# main.net
KiCad netlist of a schematic drawn in Altium Designer
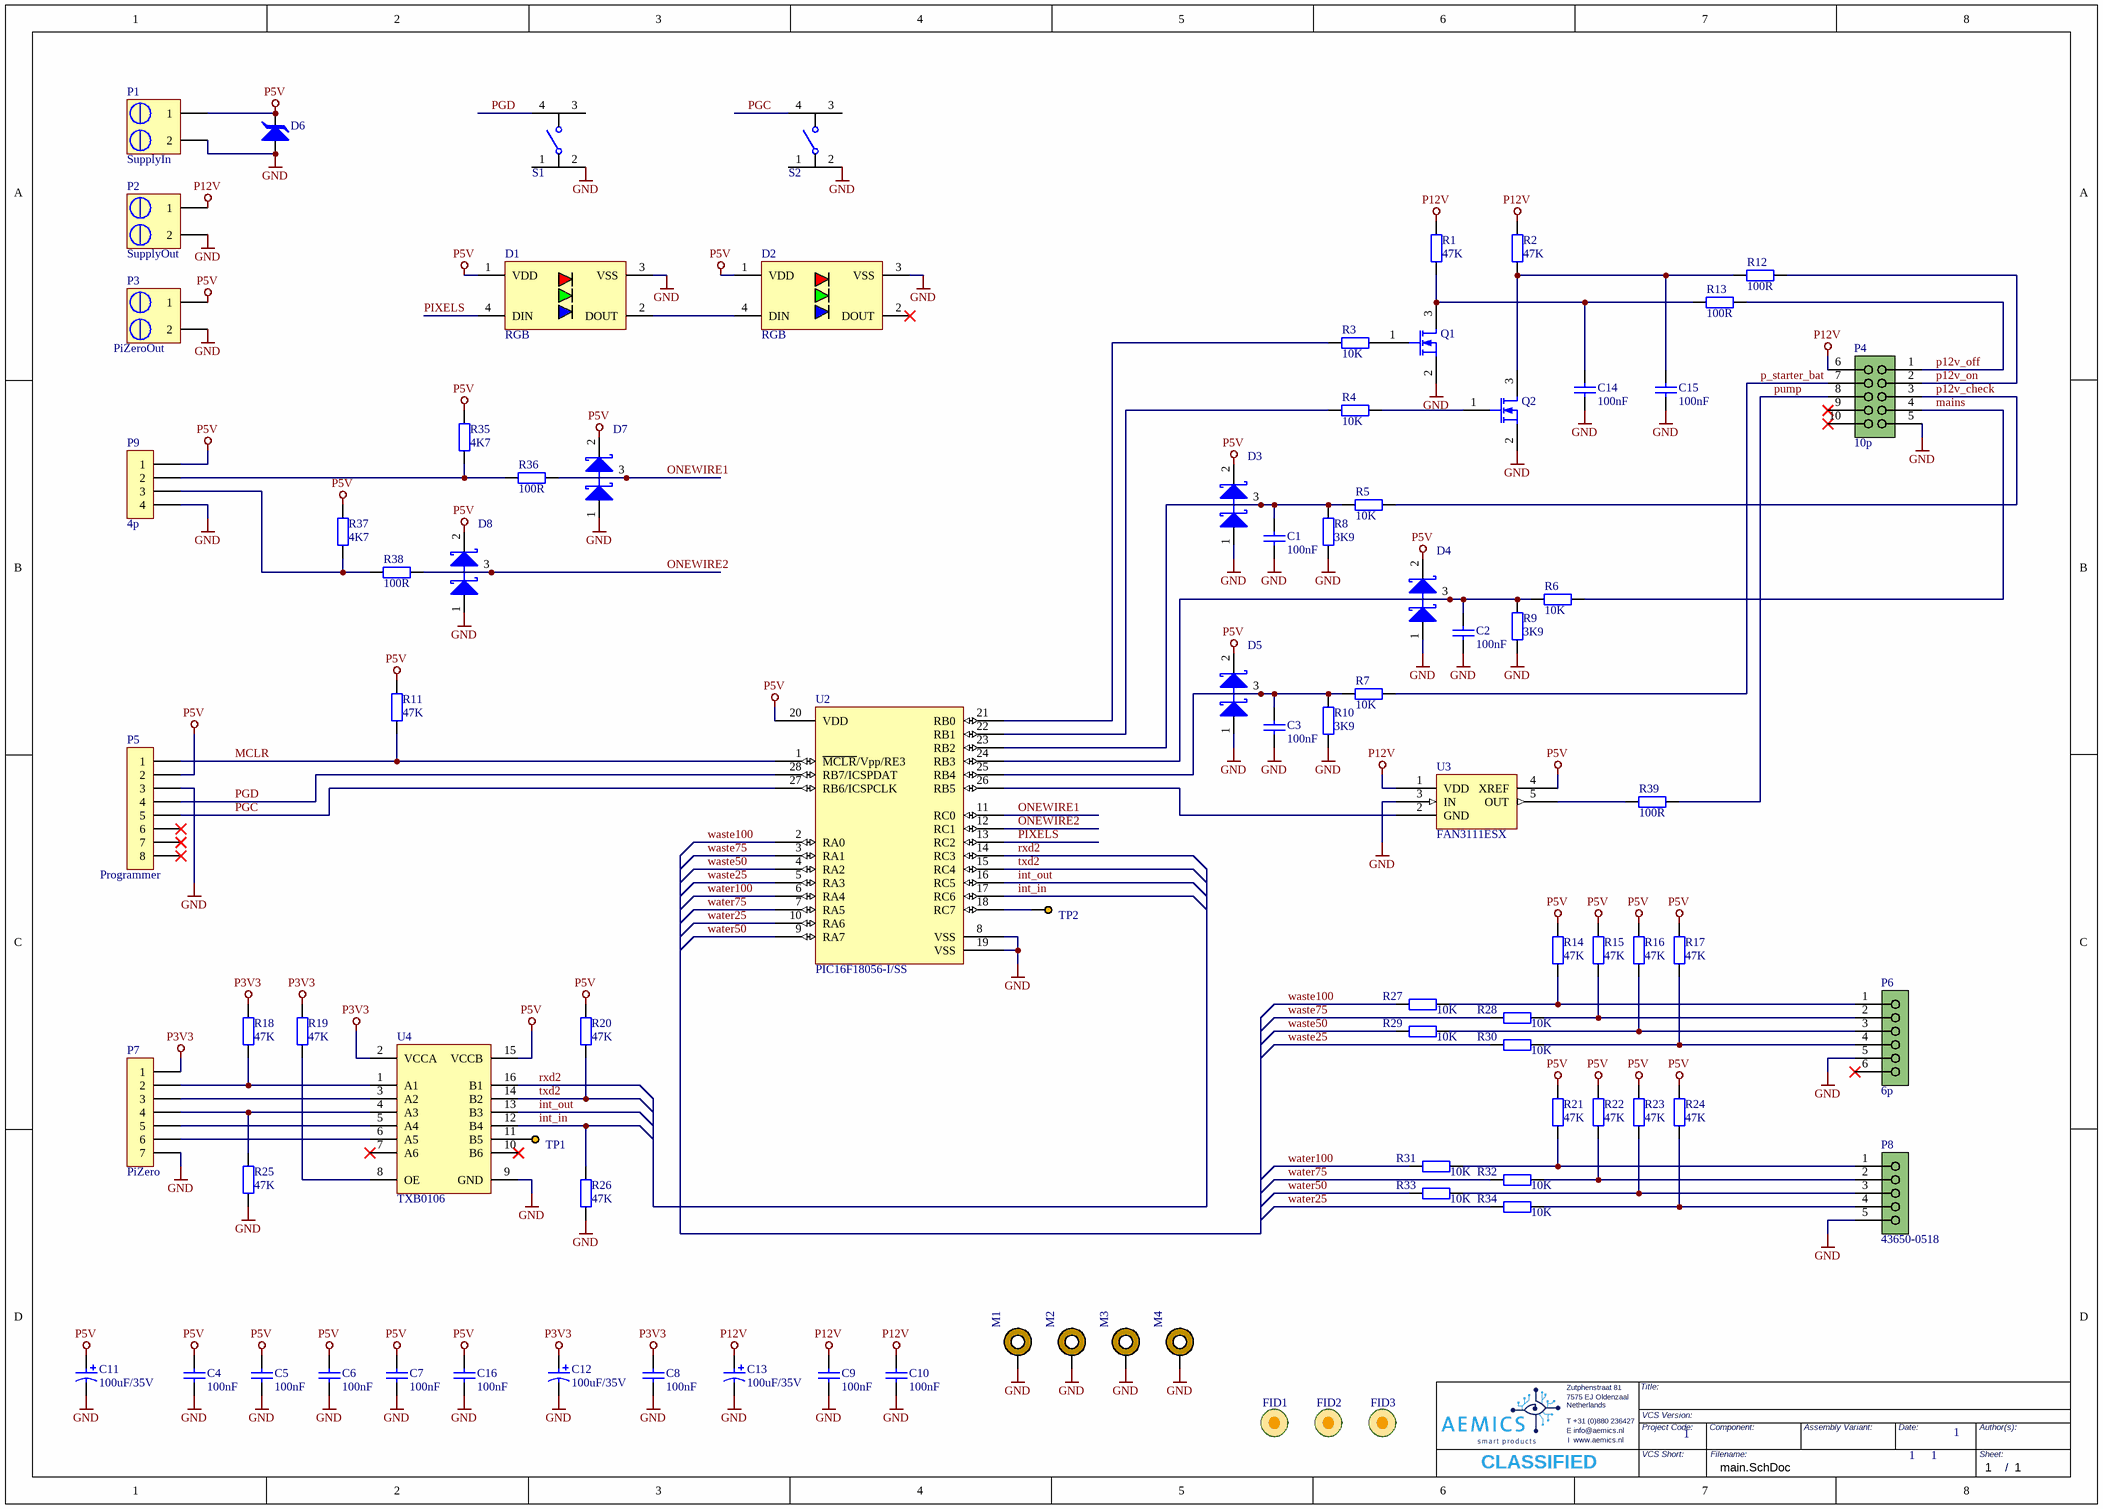
[diagram p0: main.SchDoc]

(export (version "E")
  (design (tool "Eeschema 10.0.6"))
  (components
    (comp (ref "C1")
      (value "100nF")
      (footprint "C0603")
      (description "CAP, CER, 0603, 100nF, 50V, X7R,±10%")
      (fields (field (name "Comment") "Capacitor Ceramic"))
      (libsource (lib "AECDB") (part "Capacitor Ceramic"))
    )
    (comp (ref "C2")
      (value "100nF")
      (footprint "C0603")
      (description "CAP, CER, 0603, 100nF, 50V, X7R,±10%")
      (fields (field (name "Comment") "Capacitor Ceramic"))
      (libsource (lib "AECDB") (part "Capacitor Ceramic"))
    )
    (comp (ref "C3")
      (value "100nF")
      (footprint "C0603")
      (description "CAP, CER, 0603, 100nF, 50V, X7R,±10%")
      (fields (field (name "Comment") "Capacitor Ceramic"))
      (libsource (lib "AECDB") (part "Capacitor Ceramic"))
    )
    (comp (ref "C4")
      (value "100nF")
      (footprint "C0603")
      (description "CAP, CER, 0603, 100nF, 50V, X7R,±10%")
      (fields (field (name "Comment") "Capacitor Ceramic"))
      (libsource (lib "AECDB") (part "Capacitor Ceramic"))
    )
    (comp (ref "C5")
      (value "100nF")
      (footprint "C0603")
      (description "CAP, CER, 0603, 100nF, 50V, X7R,±10%")
      (fields (field (name "Comment") "Capacitor Ceramic"))
      (libsource (lib "AECDB") (part "Capacitor Ceramic"))
    )
    (comp (ref "C6")
      (value "100nF")
      (footprint "C0603")
      (description "CAP, CER, 0603, 100nF, 50V, X7R,±10%")
      (fields (field (name "Comment") "Capacitor Ceramic"))
      (libsource (lib "AECDB") (part "Capacitor Ceramic"))
    )
    (comp (ref "C7")
      (value "100nF")
      (footprint "C0603")
      (description "CAP, CER, 0603, 100nF, 50V, X7R,±10%")
      (fields (field (name "Comment") "Capacitor Ceramic"))
      (libsource (lib "AECDB") (part "Capacitor Ceramic"))
    )
    (comp (ref "C8")
      (value "100nF")
      (footprint "C0603")
      (description "CAP, CER, 0603, 100nF, 50V, X7R,±10%")
      (fields (field (name "Comment") "Capacitor Ceramic"))
      (libsource (lib "AECDB") (part "Capacitor Ceramic"))
    )
    (comp (ref "C9")
      (value "100nF")
      (footprint "C0603")
      (description "CAP, CER, 0603, 100nF, 50V, X7R,±10%")
      (fields (field (name "Comment") "Capacitor Ceramic"))
      (libsource (lib "AECDB") (part "Capacitor Ceramic"))
    )
    (comp (ref "C10")
      (value "100nF")
      (footprint "C0603")
      (description "CAP, CER, 0603, 100nF, 50V, X7R,±10%")
      (fields (field (name "Comment") "Capacitor Ceramic"))
      (libsource (lib "AECDB") (part "Capacitor Ceramic"))
    )
    (comp (ref "C11")
      (value "100uF/35V")
      (footprint "ELCO D-PACK")
      (description "CAP, ELC, 6.3x5.8, 100uF, 35V, 20%")
      (fields (field (name "Comment") "Capacitor Electrolytic"))
      (libsource (lib "AECDB") (part "Capacitor Electrolytic"))
    )
    (comp (ref "C12")
      (value "100uF/35V")
      (footprint "ELCO D-PACK")
      (description "CAP, ELC, 6.3x5.8, 100uF, 35V, 20%")
      (fields (field (name "Comment") "Capacitor Electrolytic"))
      (libsource (lib "AECDB") (part "Capacitor Electrolytic"))
    )
    (comp (ref "C13")
      (value "100uF/35V")
      (footprint "ELCO D-PACK")
      (description "CAP, ELC, 6.3x5.8, 100uF, 35V, 20%")
      (fields (field (name "Comment") "Capacitor Electrolytic"))
      (libsource (lib "AECDB") (part "Capacitor Electrolytic"))
    )
    (comp (ref "C14")
      (value "100nF")
      (footprint "C0603")
      (description "CAP, CER, 0603, 100nF, 50V, X7R,±10%")
      (fields (field (name "Comment") "Capacitor Ceramic"))
      (libsource (lib "AECDB") (part "Capacitor Ceramic"))
    )
    (comp (ref "C15")
      (value "100nF")
      (footprint "C0603")
      (description "CAP, CER, 0603, 100nF, 50V, X7R,±10%")
      (fields (field (name "Comment") "Capacitor Ceramic"))
      (libsource (lib "AECDB") (part "Capacitor Ceramic"))
    )
    (comp (ref "C16")
      (value "100nF")
      (footprint "C0603")
      (description "CAP, CER, 0603, 100nF, 50V, X7R,±10%")
      (fields (field (name "Comment") "Capacitor Ceramic"))
      (libsource (lib "AECDB") (part "Capacitor Ceramic"))
    )
    (comp (ref "D1")
      (value "RGB")
      (footprint "WS2812B-B")
      (description "LED,Adressable,RGB")
      (fields (field (name "Comment") "WS2812B-B"))
      (libsource (lib "AECDB") (part "WS2812B-B"))
    )
    (comp (ref "D2")
      (value "RGB")
      (footprint "WS2812B-B")
      (description "LED,Adressable,RGB")
      (fields (field (name "Comment") "WS2812B-B"))
      (libsource (lib "AECDB") (part "WS2812B-B"))
    )
    (comp (ref "D3")
      (value "DIODE SCHOTTKY DUAL A1K2AK3")
      (footprint "SOT23-3")
      (description "Schottky Barrier Diode, Dual, Series")
      (libsource (lib "AECDB") (part "DIODE SCHOTTKY DUAL A1K2AK3"))
    )
    (comp (ref "D4")
      (value "DIODE SCHOTTKY DUAL A1K2AK3")
      (footprint "SOT23-3")
      (description "Schottky Barrier Diode, Dual, Series")
      (libsource (lib "AECDB") (part "DIODE SCHOTTKY DUAL A1K2AK3"))
    )
    (comp (ref "D5")
      (value "DIODE SCHOTTKY DUAL A1K2AK3")
      (footprint "SOT23-3")
      (description "Schottky Barrier Diode, Dual, Series")
      (libsource (lib "AECDB") (part "DIODE SCHOTTKY DUAL A1K2AK3"))
    )
    (comp (ref "D6")
      (value "DIODE TVS UNIDIR A1K2")
      (footprint "SOD-323")
      (description "TVS Diode, Unidirectional, 5V, 300mW")
      (libsource (lib "AECDB") (part "DIODE TVS UNIDIR A1K2"))
    )
    (comp (ref "D7")
      (value "DIODE SCHOTTKY DUAL A1K2AK3")
      (footprint "SOT23-3")
      (description "Schottky Barrier Diode, Dual, Series")
      (libsource (lib "AECDB") (part "DIODE SCHOTTKY DUAL A1K2AK3"))
    )
    (comp (ref "D8")
      (value "DIODE SCHOTTKY DUAL A1K2AK3")
      (footprint "SOT23-3")
      (description "Schottky Barrier Diode, Dual, Series")
      (libsource (lib "AECDB") (part "DIODE SCHOTTKY DUAL A1K2AK3"))
    )
    (comp (ref "FID1")
      (value "Fiducial")
      (footprint "FIDUCIAL1MM")
      (description "Fiducial Mark,Round,1mm")
      (libsource (lib "AECDB") (part "Fiducial"))
    )
    (comp (ref "FID2")
      (value "Fiducial")
      (footprint "FIDUCIAL1MM")
      (description "Fiducial Mark,Round,1mm")
      (libsource (lib "AECDB") (part "Fiducial"))
    )
    (comp (ref "FID3")
      (value "Fiducial")
      (footprint "FIDUCIAL1MM")
      (description "Fiducial Mark,Round,1mm")
      (libsource (lib "AECDB") (part "Fiducial"))
    )
    (comp (ref "M1")
      (value "PTH")
      (footprint "PTH-M2.5-D4.0")
      (description "Plated Through-Hole, M2.5")
      (libsource (lib "AECDB") (part "PTH"))
    )
    (comp (ref "M2")
      (value "PTH")
      (footprint "PTH-M2.5-D4.0")
      (description "Plated Through-Hole, M2.5")
      (libsource (lib "AECDB") (part "PTH"))
    )
    (comp (ref "M3")
      (value "PTH")
      (footprint "PTH-M2.5-D4.0")
      (description "Plated Through-Hole, M2.5")
      (libsource (lib "AECDB") (part "PTH"))
    )
    (comp (ref "M4")
      (value "PTH")
      (footprint "PTH-M2.5-D4.0")
      (description "Plated Through-Hole, M2.5")
      (libsource (lib "AECDB") (part "PTH"))
    )
    (comp (ref "P1")
      (value "SupplyIn")
      (footprint "TERMBLOCK508P-SCREW-2")
      (description "Terminal Block, 5.08mm Pitch, Screw Contacts")
      (fields (field (name "Comment") "ScrewTerminal 2p"))
      (libsource (lib "AECDB") (part "ScrewTerminal 2p"))
    )
    (comp (ref "P2")
      (value "SupplyOut")
      (footprint "TERMBLOCK508P-SCREW-2")
      (description "Terminal Block, 5.08mm Pitch, Screw Contacts")
      (fields (field (name "Comment") "ScrewTerminal 2p"))
      (libsource (lib "AECDB") (part "ScrewTerminal 2p"))
    )
    (comp (ref "P3")
      (value "PiZeroOut")
      (footprint "TERMBLOCK508P-SCREW-2")
      (description "Terminal Block, 5.08mm Pitch, Screw Contacts")
      (fields (field (name "Comment") "ScrewTerminal 2p"))
      (libsource (lib "AECDB") (part "ScrewTerminal 2p"))
    )
    (comp (ref "P4")
      (value "10p")
      (footprint "MOLEX 43045-1012")
      (description "Socket, Vertical, 2x5p,3mm")
      (fields (field (name "Comment") "SOCKET2X005"))
      (libsource (lib "AECDB") (part "SOCKET2X005"))
    )
    (comp (ref "P5")
      (value "Programmer")
      (footprint "TSW-108-07-F-S")
      (description "Samtec TSW Header,2.54mm Pitch,Single Row,Vertical")
      (fields (field (name "Comment") "HDR8x1"))
      (libsource (lib "AECDB") (part "HDR8x1"))
    )
    (comp (ref "P6")
      (value "6p")
      (footprint "MOLEX 43650-0618")
      (description "Socket, Vertical, 6p, 3mm")
      (fields (field (name "Comment") "SOCKET1X006"))
      (libsource (lib "AECDB") (part "SOCKET1X006"))
    )
    (comp (ref "P7")
      (value "PiZero")
      (footprint "HDR1X7-P254")
      (description "Samtec TSW Header,2.54mm Pitch,Single Row,Vertical")
      (fields (field (name "Comment") "HDR7x1"))
      (libsource (lib "AECDB") (part "HDR7x1"))
    )
    (comp (ref "P8")
      (value "43650-0518")
      (footprint "MOLEX 43650-0518")
      (description "Socket, Vertical, 5p, 3mm")
      (fields (field (name "Comment") "SOCKET1X005"))
      (libsource (lib "AECDB") (part "SOCKET1X005"))
    )
    (comp (ref "P9")
      (value "4p")
      (footprint "TSW-104-06-G-S")
      (description "Samtec TSW Header,Single Row,Vertical,5.21mm Height,Gold Flash")
      (fields (field (name "Comment") "HDR4x1"))
      (libsource (lib "AECDB") (part "HDR4x1"))
    )
    (comp (ref "Q1")
      (value "MOSFET N GSD")
      (footprint "SOT23-3")
      (description "MOSFET, N Channel, 310 mA, 60 V, 0.86 ohm")
      (libsource (lib "AECDB") (part "MOSFET N GSD"))
    )
    (comp (ref "Q2")
      (value "MOSFET N GSD")
      (footprint "SOT23-3")
      (description "MOSFET, N Channel, 310 mA, 60 V, 0.86 ohm")
      (libsource (lib "AECDB") (part "MOSFET N GSD"))
    )
    (comp (ref "R1")
      (value "47K")
      (footprint "R0603")
      (description "RES, 0603, 47K, 1%,100mW")
      (fields (field (name "Comment") "Resistor"))
      (libsource (lib "AECDB") (part "Resistor"))
    )
    (comp (ref "R2")
      (value "47K")
      (footprint "R0603")
      (description "RES, 0603, 47K, 1%,100mW")
      (fields (field (name "Comment") "Resistor"))
      (libsource (lib "AECDB") (part "Resistor"))
    )
    (comp (ref "R3")
      (value "10K")
      (footprint "R0603")
      (description "RES, 0603, 10K,63mW,1%")
      (fields (field (name "Comment") "Resistor"))
      (libsource (lib "") (part "Resistor_1"))
    )
    (comp (ref "R4")
      (value "10K")
      (footprint "R0603")
      (description "RES, 0603, 10K,63mW,1%")
      (fields (field (name "Comment") "Resistor"))
      (libsource (lib "") (part "Resistor_1"))
    )
    (comp (ref "R5")
      (value "10K")
      (footprint "R0603")
      (description "RES, 0603, 10K,63mW,1%")
      (fields (field (name "Comment") "Resistor"))
      (libsource (lib "") (part "Resistor_1"))
    )
    (comp (ref "R6")
      (value "10K")
      (footprint "R0603")
      (description "RES, 0603, 10K,63mW,1%")
      (fields (field (name "Comment") "Resistor"))
      (libsource (lib "") (part "Resistor_1"))
    )
    (comp (ref "R7")
      (value "10K")
      (footprint "R0603")
      (description "RES, 0603, 10K,63mW,1%")
      (fields (field (name "Comment") "Resistor"))
      (libsource (lib "") (part "Resistor_1"))
    )
    (comp (ref "R8")
      (value "3K9")
      (footprint "R0603")
      (description "RES, 0603, 3K9, 0.063W, 1%")
      (fields (field (name "Comment") "Resistor"))
      (libsource (lib "AECDB") (part "Resistor"))
    )
    (comp (ref "R9")
      (value "3K9")
      (footprint "R0603")
      (description "RES, 0603, 3K9, 0.063W, 1%")
      (fields (field (name "Comment") "Resistor"))
      (libsource (lib "AECDB") (part "Resistor"))
    )
    (comp (ref "R10")
      (value "3K9")
      (footprint "R0603")
      (description "RES, 0603, 3K9, 0.063W, 1%")
      (fields (field (name "Comment") "Resistor"))
      (libsource (lib "AECDB") (part "Resistor"))
    )
    (comp (ref "R11")
      (value "47K")
      (footprint "R0603")
      (description "RES, 0603, 47K, 1%,100mW")
      (fields (field (name "Comment") "Resistor"))
      (libsource (lib "AECDB") (part "Resistor"))
    )
    (comp (ref "R12")
      (value "100R")
      (footprint "R0603")
      (description "RES, 0603, 100R, 0.063W, 1%")
      (fields (field (name "Comment") "Resistor"))
      (libsource (lib "") (part "Resistor_2"))
    )
    (comp (ref "R13")
      (value "100R")
      (footprint "R0603")
      (description "RES, 0603, 100R, 0.063W, 1%")
      (fields (field (name "Comment") "Resistor"))
      (libsource (lib "") (part "Resistor_2"))
    )
    (comp (ref "R14")
      (value "47K")
      (footprint "R0603")
      (description "RES, 0603, 47K, 1%,100mW")
      (fields (field (name "Comment") "Resistor"))
      (libsource (lib "AECDB") (part "Resistor"))
    )
    (comp (ref "R15")
      (value "47K")
      (footprint "R0603")
      (description "RES, 0603, 47K, 1%,100mW")
      (fields (field (name "Comment") "Resistor"))
      (libsource (lib "AECDB") (part "Resistor"))
    )
    (comp (ref "R16")
      (value "47K")
      (footprint "R0603")
      (description "RES, 0603, 47K, 1%,100mW")
      (fields (field (name "Comment") "Resistor"))
      (libsource (lib "AECDB") (part "Resistor"))
    )
    (comp (ref "R17")
      (value "47K")
      (footprint "R0603")
      (description "RES, 0603, 47K, 1%,100mW")
      (fields (field (name "Comment") "Resistor"))
      (libsource (lib "AECDB") (part "Resistor"))
    )
    (comp (ref "R18")
      (value "47K")
      (footprint "R0603")
      (description "RES, 0603, 47K, 1%,100mW")
      (fields (field (name "Comment") "Resistor"))
      (libsource (lib "AECDB") (part "Resistor"))
    )
    (comp (ref "R19")
      (value "47K")
      (footprint "R0603")
      (description "RES, 0603, 47K, 1%,100mW")
      (fields (field (name "Comment") "Resistor"))
      (libsource (lib "AECDB") (part "Resistor"))
    )
    (comp (ref "R20")
      (value "47K")
      (footprint "R0603")
      (description "RES, 0603, 47K, 1%,100mW")
      (fields (field (name "Comment") "Resistor"))
      (libsource (lib "AECDB") (part "Resistor"))
    )
    (comp (ref "R21")
      (value "47K")
      (footprint "R0603")
      (description "RES, 0603, 47K, 1%,100mW")
      (fields (field (name "Comment") "Resistor"))
      (libsource (lib "AECDB") (part "Resistor"))
    )
    (comp (ref "R22")
      (value "47K")
      (footprint "R0603")
      (description "RES, 0603, 47K, 1%,100mW")
      (fields (field (name "Comment") "Resistor"))
      (libsource (lib "AECDB") (part "Resistor"))
    )
    (comp (ref "R23")
      (value "47K")
      (footprint "R0603")
      (description "RES, 0603, 47K, 1%,100mW")
      (fields (field (name "Comment") "Resistor"))
      (libsource (lib "AECDB") (part "Resistor"))
    )
    (comp (ref "R24")
      (value "47K")
      (footprint "R0603")
      (description "RES, 0603, 47K, 1%,100mW")
      (fields (field (name "Comment") "Resistor"))
      (libsource (lib "AECDB") (part "Resistor"))
    )
    (comp (ref "R25")
      (value "47K")
      (footprint "R0603")
      (description "RES, 0603, 47K, 1%,100mW")
      (fields (field (name "Comment") "Resistor"))
      (libsource (lib "AECDB") (part "Resistor"))
    )
    (comp (ref "R26")
      (value "47K")
      (footprint "R0603")
      (description "RES, 0603, 47K, 1%,100mW")
      (fields (field (name "Comment") "Resistor"))
      (libsource (lib "AECDB") (part "Resistor"))
    )
    (comp (ref "R27")
      (value "10K")
      (footprint "R0603")
      (description "RES, 0603, 10K,63mW,1%")
      (fields (field (name "Comment") "Resistor"))
      (libsource (lib "") (part "Resistor_1"))
    )
    (comp (ref "R28")
      (value "10K")
      (footprint "R0603")
      (description "RES, 0603, 10K,63mW,1%")
      (fields (field (name "Comment") "Resistor"))
      (libsource (lib "") (part "Resistor_1"))
    )
    (comp (ref "R29")
      (value "10K")
      (footprint "R0603")
      (description "RES, 0603, 10K,63mW,1%")
      (fields (field (name "Comment") "Resistor"))
      (libsource (lib "") (part "Resistor_1"))
    )
    (comp (ref "R30")
      (value "10K")
      (footprint "R0603")
      (description "RES, 0603, 10K,63mW,1%")
      (fields (field (name "Comment") "Resistor"))
      (libsource (lib "") (part "Resistor_1"))
    )
    (comp (ref "R31")
      (value "10K")
      (footprint "R0603")
      (description "RES, 0603, 10K,63mW,1%")
      (fields (field (name "Comment") "Resistor"))
      (libsource (lib "") (part "Resistor_1"))
    )
    (comp (ref "R32")
      (value "10K")
      (footprint "R0603")
      (description "RES, 0603, 10K,63mW,1%")
      (fields (field (name "Comment") "Resistor"))
      (libsource (lib "") (part "Resistor_1"))
    )
    (comp (ref "R33")
      (value "10K")
      (footprint "R0603")
      (description "RES, 0603, 10K,63mW,1%")
      (fields (field (name "Comment") "Resistor"))
      (libsource (lib "") (part "Resistor_1"))
    )
    (comp (ref "R34")
      (value "10K")
      (footprint "R0603")
      (description "RES, 0603, 10K,63mW,1%")
      (fields (field (name "Comment") "Resistor"))
      (libsource (lib "") (part "Resistor_1"))
    )
    (comp (ref "R35")
      (value "4K7")
      (footprint "R0603")
      (description "RES, 0603, 4K7, 0.063W, 1%")
      (fields (field (name "Comment") "Resistor"))
      (libsource (lib "AECDB") (part "Resistor"))
    )
    (comp (ref "R36")
      (value "100R")
      (footprint "R0603")
      (description "RES, 0603, 100R, 0.063W, 1%")
      (fields (field (name "Comment") "Resistor"))
      (libsource (lib "") (part "Resistor_2"))
    )
    (comp (ref "R37")
      (value "4K7")
      (footprint "R0603")
      (description "RES, 0603, 4K7, 0.063W, 1%")
      (fields (field (name "Comment") "Resistor"))
      (libsource (lib "AECDB") (part "Resistor"))
    )
    (comp (ref "R38")
      (value "100R")
      (footprint "R0603")
      (description "RES, 0603, 100R, 0.063W, 1%")
      (fields (field (name "Comment") "Resistor"))
      (libsource (lib "") (part "Resistor_2"))
    )
    (comp (ref "R39")
      (value "100R")
      (footprint "R0603")
      (description "RES, 0603, 100R, 0.063W, 1%")
      (fields (field (name "Comment") "Resistor"))
      (libsource (lib "") (part "Resistor_2"))
    )
    (comp (ref "S1")
      (value "WE-TATV")
      (footprint "WE-TATV")
      (description "WE TATV Series Tactile Switch, TH, 12x12mm, Square Actuator, Black")
      (libsource (lib "AECDB") (part "WE-TATV"))
    )
    (comp (ref "S2")
      (value "WE-TATV")
      (footprint "WE-TATV")
      (description "WE TATV Series Tactile Switch, TH, 12x12mm, Square Actuator, Black")
      (libsource (lib "AECDB") (part "WE-TATV"))
    )
    (comp (ref "TP1")
      (value "Testpoint")
      (footprint "TESTPAD_R2")
      (description "Test Point for PCB, Round,2mm")
      (libsource (lib "AECDB") (part "Testpoint"))
    )
    (comp (ref "TP2")
      (value "Testpoint")
      (footprint "TESTPAD_R2")
      (description "Test Point for PCB, Round,2mm")
      (libsource (lib "AECDB") (part "Testpoint"))
    )
    (comp (ref "U2")
      (value "PIC16F18056-I/SS")
      (footprint "TSOP065P07.80X10.20X02.00-28")
      (description "MCU, 8BIT, 28KB FLASH, 28SSOP")
      (fields (field (name "Comment") "PIC16F18056-ISS"))
      (libsource (lib "AECDB") (part "PIC16F18056-ISS"))
    )
    (comp (ref "U3")
      (value "FAN3111ESX")
      (footprint "SOT23-5")
      (description "Low-Side,Gate Driver,Non-Inverting,SOT-23-5")
      (fields (field (name "Comment") "FAN3111E"))
      (libsource (lib "AECDB") (part "FAN3111E"))
    )
    (comp (ref "U4")
      (value "TXB0106")
      (footprint "TSOP065P05.00X06.40X01.20-16")
      (description "6-Bit Bidirectional Level-Shifting and Voltage Translator With Auto-Direction Sensing")
      (libsource (lib "AECDB") (part "TXB0106"))
    )
  )
  (nets
    (net (code "1") (name "/MCLR") (class "Default")
      (node (ref "P5") (pin "1") (pinfunction "1_1") (pintype "passive"))
      (node (ref "R11") (pin "2") (pinfunction "2_2") (pintype "passive"))
      (node (ref "U2") (pin "1") (pinfunction "~{MCLR}/Vpp/RE3_1") (pintype "bidirectional"))
    )
    (net (code "2") (name "/ONEWIRE1") (class "Default")
      (node (ref "D7") (pin "3") (pinfunction "3_3") (pintype "passive"))
      (node (ref "R36") (pin "1") (pinfunction "1_1") (pintype "passive"))
      (node (ref "U2") (pin "11") (pinfunction "RC0_11") (pintype "bidirectional"))
    )
    (net (code "3") (name "/ONEWIRE2") (class "Default")
      (node (ref "D8") (pin "3") (pinfunction "3_3") (pintype "passive"))
      (node (ref "R38") (pin "1") (pinfunction "1_1") (pintype "passive"))
      (node (ref "U2") (pin "12") (pinfunction "RC1_12") (pintype "bidirectional"))
    )
    (net (code "4") (name "/PGC") (class "Default")
      (node (ref "P5") (pin "5") (pinfunction "5_5") (pintype "passive"))
      (node (ref "S2") (pin "4") (pinfunction "NO_4") (pintype "passive"))
      (node (ref "U2") (pin "27") (pinfunction "RB6/ICSPCLK_27") (pintype "bidirectional"))
    )
    (net (code "5") (name "/PGD") (class "Default")
      (node (ref "P5") (pin "4") (pinfunction "4_4") (pintype "passive"))
      (node (ref "S1") (pin "4") (pinfunction "NO_4") (pintype "passive"))
      (node (ref "U2") (pin "28") (pinfunction "RB7/ICSPDAT_28") (pintype "bidirectional"))
    )
    (net (code "6") (name "/PIXELS") (class "Default")
      (node (ref "D1") (pin "4") (pinfunction "DIN_4") (pintype "passive"))
      (node (ref "U2") (pin "13") (pinfunction "RC2_13") (pintype "bidirectional"))
    )
    (net (code "7") (name "/int_in") (class "Default")
      (node (ref "R26") (pin "1") (pinfunction "1_1") (pintype "passive"))
      (node (ref "U2") (pin "17") (pinfunction "RC6_17") (pintype "bidirectional"))
      (node (ref "U4") (pin "12") (pinfunction "B4_12") (pintype "passive"))
    )
    (net (code "8") (name "/int_out") (class "Default")
      (node (ref "U2") (pin "16") (pinfunction "RC5_16") (pintype "bidirectional"))
      (node (ref "U4") (pin "13") (pinfunction "B3_13") (pintype "passive"))
    )
    (net (code "9") (name "/mains") (class "Default")
      (node (ref "P4") (pin "4") (pinfunction "4_4") (pintype "passive"))
      (node (ref "R6") (pin "2") (pinfunction "2_2") (pintype "passive"))
    )
    (net (code "10") (name "/p12v_check") (class "Default")
      (node (ref "P4") (pin "3") (pinfunction "3_3") (pintype "passive"))
      (node (ref "R5") (pin "2") (pinfunction "2_2") (pintype "passive"))
    )
    (net (code "11") (name "/p12v_off") (class "Default")
      (node (ref "P4") (pin "1") (pinfunction "1_1") (pintype "passive"))
      (node (ref "R13") (pin "1") (pinfunction "1_1") (pintype "passive"))
    )
    (net (code "12") (name "/p12v_on") (class "Default")
      (node (ref "P4") (pin "2") (pinfunction "2_2") (pintype "passive"))
      (node (ref "R12") (pin "1") (pinfunction "1_1") (pintype "passive"))
    )
    (net (code "13") (name "/p_starter_bat") (class "Default")
      (node (ref "P4") (pin "7") (pinfunction "7_7") (pintype "passive"))
      (node (ref "R7") (pin "2") (pinfunction "2_2") (pintype "passive"))
    )
    (net (code "14") (name "/pump") (class "Default")
      (node (ref "P4") (pin "8") (pinfunction "8_8") (pintype "passive"))
      (node (ref "R39") (pin "1") (pinfunction "1_1") (pintype "passive"))
    )
    (net (code "15") (name "/rxd2") (class "Default")
      (node (ref "U2") (pin "14") (pinfunction "RC3_14") (pintype "bidirectional"))
      (node (ref "U4") (pin "16") (pinfunction "B1_16") (pintype "passive"))
    )
    (net (code "16") (name "/txd2") (class "Default")
      (node (ref "R20") (pin "2") (pinfunction "2_2") (pintype "passive"))
      (node (ref "U2") (pin "15") (pinfunction "RC4_15") (pintype "bidirectional"))
      (node (ref "U4") (pin "14") (pinfunction "B2_14") (pintype "passive"))
    )
    (net (code "17") (name "/waste25") (class "Default")
      (node (ref "R30") (pin "1") (pinfunction "1_1") (pintype "passive"))
      (node (ref "U2") (pin "5") (pinfunction "RA3_5") (pintype "bidirectional"))
    )
    (net (code "18") (name "/waste50") (class "Default")
      (node (ref "R29") (pin "1") (pinfunction "1_1") (pintype "passive"))
      (node (ref "U2") (pin "4") (pinfunction "RA2_4") (pintype "bidirectional"))
    )
    (net (code "19") (name "/waste75") (class "Default")
      (node (ref "R28") (pin "1") (pinfunction "1_1") (pintype "passive"))
      (node (ref "U2") (pin "3") (pinfunction "RA1_3") (pintype "bidirectional"))
    )
    (net (code "20") (name "/waste100") (class "Default")
      (node (ref "R27") (pin "1") (pinfunction "1_1") (pintype "passive"))
      (node (ref "U2") (pin "2") (pinfunction "RA0_2") (pintype "bidirectional"))
    )
    (net (code "21") (name "/water25") (class "Default")
      (node (ref "R34") (pin "1") (pinfunction "1_1") (pintype "passive"))
      (node (ref "U2") (pin "10") (pinfunction "RA6_10") (pintype "bidirectional"))
    )
    (net (code "22") (name "/water50") (class "Default")
      (node (ref "R33") (pin "1") (pinfunction "1_1") (pintype "passive"))
      (node (ref "U2") (pin "9") (pinfunction "RA7_9") (pintype "bidirectional"))
    )
    (net (code "23") (name "/water75") (class "Default")
      (node (ref "R32") (pin "1") (pinfunction "1_1") (pintype "passive"))
      (node (ref "U2") (pin "7") (pinfunction "RA5_7") (pintype "bidirectional"))
    )
    (net (code "24") (name "/water100") (class "Default")
      (node (ref "R31") (pin "1") (pinfunction "1_1") (pintype "passive"))
      (node (ref "U2") (pin "6") (pinfunction "RA4_6") (pintype "bidirectional"))
    )
    (net (code "25") (name "GND") (class "Default")
      (node (ref "C1") (pin "2") (pinfunction "2_2") (pintype "passive"))
      (node (ref "C10") (pin "2") (pinfunction "2_2") (pintype "passive"))
      (node (ref "C11") (pin "2") (pinfunction "2_2") (pintype "passive"))
      (node (ref "C12") (pin "2") (pinfunction "2_2") (pintype "passive"))
      (node (ref "C13") (pin "2") (pinfunction "2_2") (pintype "passive"))
      (node (ref "C14") (pin "2") (pinfunction "2_2") (pintype "passive"))
      (node (ref "C15") (pin "2") (pinfunction "2_2") (pintype "passive"))
      (node (ref "C16") (pin "2") (pinfunction "2_2") (pintype "passive"))
      (node (ref "C2") (pin "2") (pinfunction "2_2") (pintype "passive"))
      (node (ref "C3") (pin "2") (pinfunction "2_2") (pintype "passive"))
      (node (ref "C4") (pin "2") (pinfunction "2_2") (pintype "passive"))
      (node (ref "C5") (pin "2") (pinfunction "2_2") (pintype "passive"))
      (node (ref "C6") (pin "2") (pinfunction "2_2") (pintype "passive"))
      (node (ref "C7") (pin "2") (pinfunction "2_2") (pintype "passive"))
      (node (ref "C8") (pin "2") (pinfunction "2_2") (pintype "passive"))
      (node (ref "C9") (pin "2") (pinfunction "2_2") (pintype "passive"))
      (node (ref "D1") (pin "3") (pinfunction "VSS_3") (pintype "passive"))
      (node (ref "D2") (pin "3") (pinfunction "VSS_3") (pintype "passive"))
      (node (ref "D3") (pin "1") (pinfunction "A_1") (pintype "passive"))
      (node (ref "D4") (pin "1") (pinfunction "A_1") (pintype "passive"))
      (node (ref "D5") (pin "1") (pinfunction "A_1") (pintype "passive"))
      (node (ref "D6") (pin "1") (pinfunction "A_1") (pintype "passive"))
      (node (ref "D7") (pin "1") (pinfunction "A_1") (pintype "passive"))
      (node (ref "D8") (pin "1") (pinfunction "A_1") (pintype "passive"))
      (node (ref "M1") (pin "1") (pinfunction "1_1") (pintype "passive"))
      (node (ref "M2") (pin "1") (pinfunction "1_1") (pintype "passive"))
      (node (ref "M3") (pin "1") (pinfunction "1_1") (pintype "passive"))
      (node (ref "M4") (pin "1") (pinfunction "1_1") (pintype "passive"))
      (node (ref "P1") (pin "2") (pinfunction "2_2") (pintype "passive"))
      (node (ref "P2") (pin "2") (pinfunction "2_2") (pintype "passive"))
      (node (ref "P3") (pin "2") (pinfunction "2_2") (pintype "passive"))
      (node (ref "P4") (pin "5") (pinfunction "5_5") (pintype "passive"))
      (node (ref "P5") (pin "3") (pinfunction "3_3") (pintype "passive"))
      (node (ref "P6") (pin "5") (pinfunction "5_5") (pintype "passive"))
      (node (ref "P7") (pin "7") (pinfunction "7_7") (pintype "passive"))
      (node (ref "P8") (pin "5") (pinfunction "5_5") (pintype "passive"))
      (node (ref "P9") (pin "4") (pinfunction "4_4") (pintype "passive"))
      (node (ref "Q1") (pin "2") (pinfunction "S_2") (pintype "passive"))
      (node (ref "Q2") (pin "2") (pinfunction "S_2") (pintype "passive"))
      (node (ref "R10") (pin "2") (pinfunction "2_2") (pintype "passive"))
      (node (ref "R25") (pin "2") (pinfunction "2_2") (pintype "passive"))
      (node (ref "R26") (pin "2") (pinfunction "2_2") (pintype "passive"))
      (node (ref "R8") (pin "2") (pinfunction "2_2") (pintype "passive"))
      (node (ref "R9") (pin "2") (pinfunction "2_2") (pintype "passive"))
      (node (ref "S1") (pin "2") (pinfunction "COMMON1_2") (pintype "passive"))
      (node (ref "S2") (pin "2") (pinfunction "COMMON1_2") (pintype "passive"))
      (node (ref "U2") (pin "19") (pinfunction "VSS_19") (pintype "power_in"))
      (node (ref "U2") (pin "8") (pinfunction "VSS_8") (pintype "power_in"))
      (node (ref "U3") (pin "3") (pinfunction "IN_3") (pintype "input"))
      (node (ref "U4") (pin "9") (pinfunction "GND_9") (pintype "passive"))
    )
    (net (code "26") (name "Net-(D1-DOUT)") (class "Default")
      (node (ref "D1") (pin "2") (pinfunction "DOUT_2") (pintype "passive"))
      (node (ref "D2") (pin "4") (pinfunction "DIN_4") (pintype "passive"))
    )
    (net (code "27") (name "Net-(P6-Pad1)") (class "Default")
      (node (ref "P6") (pin "1") (pinfunction "1_1") (pintype "passive"))
      (node (ref "R14") (pin "2") (pinfunction "2_2") (pintype "passive"))
      (node (ref "R27") (pin "2") (pinfunction "2_2") (pintype "passive"))
    )
    (net (code "28") (name "Net-(P6-Pad2)") (class "Default")
      (node (ref "P6") (pin "2") (pinfunction "2_2") (pintype "passive"))
      (node (ref "R15") (pin "2") (pinfunction "2_2") (pintype "passive"))
      (node (ref "R28") (pin "2") (pinfunction "2_2") (pintype "passive"))
    )
    (net (code "29") (name "Net-(P6-Pad3)") (class "Default")
      (node (ref "P6") (pin "3") (pinfunction "3_3") (pintype "passive"))
      (node (ref "R16") (pin "2") (pinfunction "2_2") (pintype "passive"))
      (node (ref "R29") (pin "2") (pinfunction "2_2") (pintype "passive"))
    )
    (net (code "30") (name "Net-(P6-Pad4)") (class "Default")
      (node (ref "P6") (pin "4") (pinfunction "4_4") (pintype "passive"))
      (node (ref "R17") (pin "2") (pinfunction "2_2") (pintype "passive"))
      (node (ref "R30") (pin "2") (pinfunction "2_2") (pintype "passive"))
    )
    (net (code "31") (name "Net-(P8-Pad1)") (class "Default")
      (node (ref "P8") (pin "1") (pinfunction "1_1") (pintype "passive"))
      (node (ref "R21") (pin "2") (pinfunction "2_2") (pintype "passive"))
      (node (ref "R31") (pin "2") (pinfunction "2_2") (pintype "passive"))
    )
    (net (code "32") (name "Net-(P8-Pad2)") (class "Default")
      (node (ref "P8") (pin "2") (pinfunction "2_2") (pintype "passive"))
      (node (ref "R22") (pin "2") (pinfunction "2_2") (pintype "passive"))
      (node (ref "R32") (pin "2") (pinfunction "2_2") (pintype "passive"))
    )
    (net (code "33") (name "Net-(P8-Pad3)") (class "Default")
      (node (ref "P8") (pin "3") (pinfunction "3_3") (pintype "passive"))
      (node (ref "R23") (pin "2") (pinfunction "2_2") (pintype "passive"))
      (node (ref "R33") (pin "2") (pinfunction "2_2") (pintype "passive"))
    )
    (net (code "34") (name "Net-(P8-Pad4)") (class "Default")
      (node (ref "P8") (pin "4") (pinfunction "4_4") (pintype "passive"))
      (node (ref "R24") (pin "2") (pinfunction "2_2") (pintype "passive"))
      (node (ref "R34") (pin "2") (pinfunction "2_2") (pintype "passive"))
    )
    (net (code "35") (name "Net-(P9-Pad2)") (class "Default")
      (node (ref "P9") (pin "2") (pinfunction "2_2") (pintype "passive"))
      (node (ref "R35") (pin "2") (pinfunction "2_2") (pintype "passive"))
      (node (ref "R36") (pin "2") (pinfunction "2_2") (pintype "passive"))
    )
    (net (code "36") (name "Net-(P9-Pad3)") (class "Default")
      (node (ref "P9") (pin "3") (pinfunction "3_3") (pintype "passive"))
      (node (ref "R37") (pin "2") (pinfunction "2_2") (pintype "passive"))
      (node (ref "R38") (pin "2") (pinfunction "2_2") (pintype "passive"))
    )
    (net (code "37") (name "Net-(Q1-D)") (class "Default")
      (node (ref "C14") (pin "1") (pinfunction "1_1") (pintype "passive"))
      (node (ref "Q1") (pin "3") (pinfunction "D_3") (pintype "passive"))
      (node (ref "R1") (pin "2") (pinfunction "2_2") (pintype "passive"))
      (node (ref "R13") (pin "2") (pinfunction "2_2") (pintype "passive"))
    )
    (net (code "38") (name "Net-(Q1-G)") (class "Default")
      (node (ref "Q1") (pin "1") (pinfunction "G_1") (pintype "passive"))
      (node (ref "R3") (pin "2") (pinfunction "2_2") (pintype "passive"))
    )
    (net (code "39") (name "Net-(Q2-D)") (class "Default")
      (node (ref "C15") (pin "1") (pinfunction "1_1") (pintype "passive"))
      (node (ref "Q2") (pin "3") (pinfunction "D_3") (pintype "passive"))
      (node (ref "R12") (pin "2") (pinfunction "2_2") (pintype "passive"))
      (node (ref "R2") (pin "2") (pinfunction "2_2") (pintype "passive"))
    )
    (net (code "40") (name "Net-(Q2-G)") (class "Default")
      (node (ref "Q2") (pin "1") (pinfunction "G_1") (pintype "passive"))
      (node (ref "R4") (pin "2") (pinfunction "2_2") (pintype "passive"))
    )
    (net (code "41") (name "Net-(TP1-pin_1)") (class "Default")
      (node (ref "TP1") (pin "1") (pinfunction "pin_1_1") (pintype "passive"))
      (node (ref "U4") (pin "11") (pinfunction "B5_11") (pintype "passive"))
    )
    (net (code "42") (name "Net-(TP2-pin_1)") (class "Default")
      (node (ref "TP2") (pin "1") (pinfunction "pin_1_1") (pintype "passive"))
      (node (ref "U2") (pin "18") (pinfunction "RC7_18") (pintype "bidirectional"))
    )
    (net (code "43") (name "Net-(U2-RB0)") (class "Default")
      (node (ref "R3") (pin "1") (pinfunction "1_1") (pintype "passive"))
      (node (ref "U2") (pin "21") (pinfunction "RB0_21") (pintype "bidirectional"))
    )
    (net (code "44") (name "Net-(U2-RB1)") (class "Default")
      (node (ref "R4") (pin "1") (pinfunction "1_1") (pintype "passive"))
      (node (ref "U2") (pin "22") (pinfunction "RB1_22") (pintype "bidirectional"))
    )
    (net (code "45") (name "Net-(U2-RB2)") (class "Default")
      (node (ref "C1") (pin "1") (pinfunction "1_1") (pintype "passive"))
      (node (ref "D3") (pin "3") (pinfunction "3_3") (pintype "passive"))
      (node (ref "R5") (pin "1") (pinfunction "1_1") (pintype "passive"))
      (node (ref "R8") (pin "1") (pinfunction "1_1") (pintype "passive"))
      (node (ref "U2") (pin "23") (pinfunction "RB2_23") (pintype "bidirectional"))
    )
    (net (code "46") (name "Net-(U2-RB3)") (class "Default")
      (node (ref "C2") (pin "1") (pinfunction "1_1") (pintype "passive"))
      (node (ref "D4") (pin "3") (pinfunction "3_3") (pintype "passive"))
      (node (ref "R6") (pin "1") (pinfunction "1_1") (pintype "passive"))
      (node (ref "R9") (pin "1") (pinfunction "1_1") (pintype "passive"))
      (node (ref "U2") (pin "24") (pinfunction "RB3_24") (pintype "bidirectional"))
    )
    (net (code "47") (name "Net-(U2-RB4)") (class "Default")
      (node (ref "C3") (pin "1") (pinfunction "1_1") (pintype "passive"))
      (node (ref "D5") (pin "3") (pinfunction "3_3") (pintype "passive"))
      (node (ref "R10") (pin "1") (pinfunction "1_1") (pintype "passive"))
      (node (ref "R7") (pin "1") (pinfunction "1_1") (pintype "passive"))
      (node (ref "U2") (pin "25") (pinfunction "RB4_25") (pintype "bidirectional"))
    )
    (net (code "48") (name "Net-(U2-RB5)") (class "Default")
      (node (ref "U2") (pin "26") (pinfunction "RB5_26") (pintype "bidirectional"))
      (node (ref "U3") (pin "2") (pinfunction "GND_2") (pintype "passive"))
    )
    (net (code "49") (name "Net-(U3-OUT)") (class "Default")
      (node (ref "R39") (pin "2") (pinfunction "2_2") (pintype "passive"))
      (node (ref "U3") (pin "5") (pinfunction "OUT_5") (pintype "output"))
    )
    (net (code "50") (name "Net-(U4-A1)") (class "Default")
      (node (ref "P7") (pin "2") (pinfunction "2_2") (pintype "passive"))
      (node (ref "R18") (pin "2") (pinfunction "2_2") (pintype "passive"))
      (node (ref "U4") (pin "1") (pinfunction "A1_1") (pintype "passive"))
    )
    (net (code "51") (name "Net-(U4-A2)") (class "Default")
      (node (ref "P7") (pin "3") (pinfunction "3_3") (pintype "passive"))
      (node (ref "U4") (pin "3") (pinfunction "A2_3") (pintype "passive"))
    )
    (net (code "52") (name "Net-(U4-A3)") (class "Default")
      (node (ref "P7") (pin "4") (pinfunction "4_4") (pintype "passive"))
      (node (ref "R25") (pin "1") (pinfunction "1_1") (pintype "passive"))
      (node (ref "U4") (pin "4") (pinfunction "A3_4") (pintype "passive"))
    )
    (net (code "53") (name "Net-(U4-A4)") (class "Default")
      (node (ref "P7") (pin "5") (pinfunction "5_5") (pintype "passive"))
      (node (ref "U4") (pin "5") (pinfunction "A4_5") (pintype "passive"))
    )
    (net (code "54") (name "Net-(U4-A5)") (class "Default")
      (node (ref "P7") (pin "6") (pinfunction "6_6") (pintype "passive"))
      (node (ref "U4") (pin "6") (pinfunction "A5_6") (pintype "passive"))
    )
    (net (code "55") (name "Net-(U4-OE)") (class "Default")
      (node (ref "R19") (pin "2") (pinfunction "2_2") (pintype "passive"))
      (node (ref "U4") (pin "8") (pinfunction "OE_8") (pintype "passive"))
    )
    (net (code "56") (name "P3V3") (class "Default")
      (node (ref "C12") (pin "1") (pinfunction "1_1") (pintype "passive"))
      (node (ref "C8") (pin "1") (pinfunction "1_1") (pintype "passive"))
      (node (ref "P7") (pin "1") (pinfunction "1_1") (pintype "passive"))
      (node (ref "R18") (pin "1") (pinfunction "1_1") (pintype "passive"))
      (node (ref "R19") (pin "1") (pinfunction "1_1") (pintype "passive"))
      (node (ref "U4") (pin "2") (pinfunction "VCCA_2") (pintype "power_in"))
    )
    (net (code "57") (name "P5V") (class "Default")
      (node (ref "C11") (pin "1") (pinfunction "1_1") (pintype "passive"))
      (node (ref "C16") (pin "1") (pinfunction "1_1") (pintype "passive"))
      (node (ref "C4") (pin "1") (pinfunction "1_1") (pintype "passive"))
      (node (ref "C5") (pin "1") (pinfunction "1_1") (pintype "passive"))
      (node (ref "C6") (pin "1") (pinfunction "1_1") (pintype "passive"))
      (node (ref "C7") (pin "1") (pinfunction "1_1") (pintype "passive"))
      (node (ref "D1") (pin "1") (pinfunction "VDD_1") (pintype "passive"))
      (node (ref "D2") (pin "1") (pinfunction "VDD_1") (pintype "passive"))
      (node (ref "D3") (pin "2") (pinfunction "K_2") (pintype "passive"))
      (node (ref "D4") (pin "2") (pinfunction "K_2") (pintype "passive"))
      (node (ref "D5") (pin "2") (pinfunction "K_2") (pintype "passive"))
      (node (ref "D6") (pin "2") (pinfunction "K_2") (pintype "passive"))
      (node (ref "D7") (pin "2") (pinfunction "K_2") (pintype "passive"))
      (node (ref "D8") (pin "2") (pinfunction "K_2") (pintype "passive"))
      (node (ref "P1") (pin "1") (pinfunction "1_1") (pintype "passive"))
      (node (ref "P3") (pin "1") (pinfunction "1_1") (pintype "passive"))
      (node (ref "P5") (pin "2") (pinfunction "2_2") (pintype "passive"))
      (node (ref "P9") (pin "1") (pinfunction "1_1") (pintype "passive"))
      (node (ref "R11") (pin "1") (pinfunction "1_1") (pintype "passive"))
      (node (ref "R14") (pin "1") (pinfunction "1_1") (pintype "passive"))
      (node (ref "R15") (pin "1") (pinfunction "1_1") (pintype "passive"))
      (node (ref "R16") (pin "1") (pinfunction "1_1") (pintype "passive"))
      (node (ref "R17") (pin "1") (pinfunction "1_1") (pintype "passive"))
      (node (ref "R20") (pin "1") (pinfunction "1_1") (pintype "passive"))
      (node (ref "R21") (pin "1") (pinfunction "1_1") (pintype "passive"))
      (node (ref "R22") (pin "1") (pinfunction "1_1") (pintype "passive"))
      (node (ref "R23") (pin "1") (pinfunction "1_1") (pintype "passive"))
      (node (ref "R24") (pin "1") (pinfunction "1_1") (pintype "passive"))
      (node (ref "R35") (pin "1") (pinfunction "1_1") (pintype "passive"))
      (node (ref "R37") (pin "1") (pinfunction "1_1") (pintype "passive"))
      (node (ref "U2") (pin "20") (pinfunction "VDD_20") (pintype "power_in"))
      (node (ref "U3") (pin "4") (pinfunction "XREF_4") (pintype "passive"))
      (node (ref "U4") (pin "15") (pinfunction "VCCB_15") (pintype "passive"))
    )
    (net (code "58") (name "P12V") (class "Default")
      (node (ref "C10") (pin "1") (pinfunction "1_1") (pintype "passive"))
      (node (ref "C13") (pin "1") (pinfunction "1_1") (pintype "passive"))
      (node (ref "C9") (pin "1") (pinfunction "1_1") (pintype "passive"))
      (node (ref "P2") (pin "1") (pinfunction "1_1") (pintype "passive"))
      (node (ref "P4") (pin "6") (pinfunction "6_6") (pintype "passive"))
      (node (ref "R1") (pin "1") (pinfunction "1_1") (pintype "passive"))
      (node (ref "R2") (pin "1") (pinfunction "1_1") (pintype "passive"))
      (node (ref "U3") (pin "1") (pinfunction "VDD_1") (pintype "power_in"))
    )
    (net (code "59") (name "unconnected-(D2-DOUT-Pad2)") (class "Default")
      (node (ref "D2") (pin "2") (pinfunction "DOUT_2") (pintype "passive+no_connect"))
    )
    (net (code "60") (name "unconnected-(P4-Pad9)") (class "Default")
      (node (ref "P4") (pin "9") (pinfunction "9_9") (pintype "passive+no_connect"))
    )
    (net (code "61") (name "unconnected-(P4-Pad10)") (class "Default")
      (node (ref "P4") (pin "10") (pinfunction "10_10") (pintype "passive+no_connect"))
    )
    (net (code "62") (name "unconnected-(P5-Pad6)") (class "Default")
      (node (ref "P5") (pin "6") (pinfunction "6_6") (pintype "passive+no_connect"))
    )
    (net (code "63") (name "unconnected-(P5-Pad7)") (class "Default")
      (node (ref "P5") (pin "7") (pinfunction "7_7") (pintype "passive+no_connect"))
    )
    (net (code "64") (name "unconnected-(P5-Pad8)") (class "Default")
      (node (ref "P5") (pin "8") (pinfunction "8_8") (pintype "passive+no_connect"))
    )
    (net (code "65") (name "unconnected-(P6-Pad6)") (class "Default")
      (node (ref "P6") (pin "6") (pinfunction "6_6") (pintype "passive+no_connect"))
    )
    (net (code "66") (name "unconnected-(S1-NC-Pad1)") (class "Default")
      (node (ref "S1") (pin "1") (pinfunction "NC_1") (pintype "passive"))
    )
    (net (code "67") (name "unconnected-(S1-NO-Pad3)") (class "Default")
      (node (ref "S1") (pin "3") (pinfunction "NO_3") (pintype "passive"))
    )
    (net (code "68") (name "unconnected-(S2-NC-Pad1)") (class "Default")
      (node (ref "S2") (pin "1") (pinfunction "NC_1") (pintype "passive"))
    )
    (net (code "69") (name "unconnected-(S2-NO-Pad3)") (class "Default")
      (node (ref "S2") (pin "3") (pinfunction "NO_3") (pintype "passive"))
    )
    (net (code "70") (name "unconnected-(U4-A6-Pad7)") (class "Default")
      (node (ref "U4") (pin "7") (pinfunction "A6_7") (pintype "passive+no_connect"))
    )
    (net (code "71") (name "unconnected-(U4-B6-Pad10)") (class "Default")
      (node (ref "U4") (pin "10") (pinfunction "B6_10") (pintype "passive+no_connect"))
    )
  )
)
